# esp32-controller.net
KiCad netlist of a schematic drawn in EAGLE
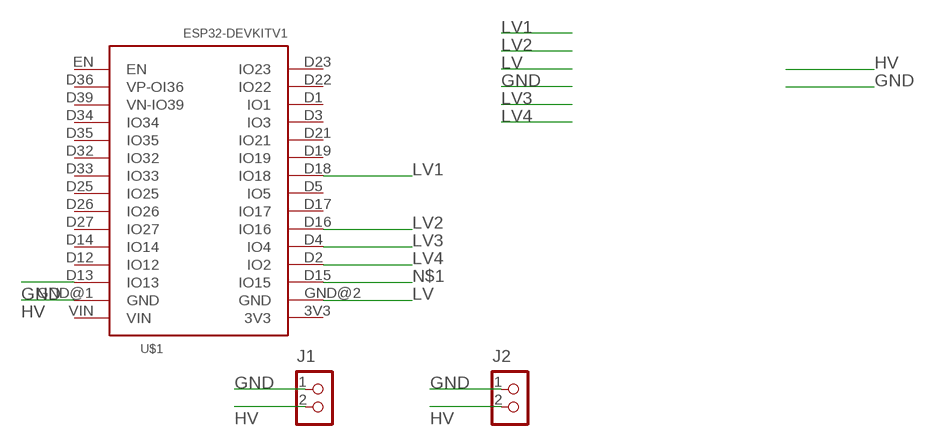
[diagram p0: schematic, sheet 1]

(export (version "E")
  (design (tool "Eeschema 10.0.6"))
  (components
    (comp (ref "J1")
      (value "CON_TERMINAL_BLOCK_02-5MM")
      (footprint "eagle-import:TERMINAL_BLOCK_2P_5")
      (libsource (lib "eagle-import") (part "CON_TERMINAL_BLOCK_02-5MM"))
    )
    (comp (ref "J2")
      (value "CON_TERMINAL_BLOCK_02-5MM")
      (footprint "eagle-import:TERMINAL_BLOCK_2P_5")
      (libsource (lib "eagle-import") (part "CON_TERMINAL_BLOCK_02-5MM"))
    )
    (comp (ref "U$1")
      (value "ESP32DEVKITV1")
      (footprint "eagle-import:ESP32-DEVKITV1")
      (libsource (lib "eagle-import") (part "ESP32DEVKITV1"))
    )
  )
  (nets
    (net (code "1") (name "/GND") (class "Default")
      (node (ref "J1") (pin "1") (pinfunction "1_1") (pintype "passive"))
      (node (ref "J2") (pin "1") (pinfunction "1_1") (pintype "passive"))
      (node (ref "U$1") (pin "D13") (pinfunction "IO13_D13") (pintype "bidirectional"))
    )
    (net (code "2") (name "/HV") (class "Default")
      (node (ref "J1") (pin "2") (pinfunction "2_2") (pintype "passive"))
      (node (ref "J2") (pin "2") (pinfunction "2_2") (pintype "passive"))
      (node (ref "U$1") (pin "GND@1") (pinfunction "GND_GND@1") (pintype "bidirectional"))
    )
    (net (code "3") (name "/LV") (class "Default")
      (node (ref "U$1") (pin "GND@2") (pinfunction "GND_GND@2") (pintype "bidirectional"))
    )
    (net (code "4") (name "/LV1") (class "Default")
      (node (ref "U$1") (pin "D18") (pinfunction "IO18_D18") (pintype "bidirectional"))
    )
    (net (code "5") (name "/LV2") (class "Default")
      (node (ref "U$1") (pin "D16") (pinfunction "IO16_D16") (pintype "bidirectional"))
    )
    (net (code "6") (name "/LV3") (class "Default")
      (node (ref "U$1") (pin "D4") (pinfunction "IO4_D4") (pintype "bidirectional"))
    )
    (net (code "7") (name "/LV4") (class "Default")
      (node (ref "U$1") (pin "D2") (pinfunction "IO2_D2") (pintype "bidirectional"))
    )
    (net (code "8") (name "/N$1") (class "Default")
      (node (ref "U$1") (pin "D15") (pinfunction "IO15_D15") (pintype "bidirectional"))
    )
    (net (code "9") (name "unconnected-(U$1-IO1-PadD1)") (class "Default")
      (node (ref "U$1") (pin "D1") (pinfunction "IO1_D1") (pintype "bidirectional"))
    )
    (net (code "10") (name "unconnected-(U$1-IO3-PadD3)") (class "Default")
      (node (ref "U$1") (pin "D3") (pinfunction "IO3_D3") (pintype "bidirectional"))
    )
    (net (code "11") (name "unconnected-(U$1-IO5-PadD5)") (class "Default")
      (node (ref "U$1") (pin "D5") (pinfunction "IO5_D5") (pintype "bidirectional"))
    )
    (net (code "12") (name "unconnected-(U$1-IO12-PadD12)") (class "Default")
      (node (ref "U$1") (pin "D12") (pinfunction "IO12_D12") (pintype "bidirectional"))
    )
    (net (code "13") (name "unconnected-(U$1-IO14-PadD14)") (class "Default")
      (node (ref "U$1") (pin "D14") (pinfunction "IO14_D14") (pintype "bidirectional"))
    )
    (net (code "14") (name "unconnected-(U$1-IO17-PadD17)") (class "Default")
      (node (ref "U$1") (pin "D17") (pinfunction "IO17_D17") (pintype "bidirectional"))
    )
    (net (code "15") (name "unconnected-(U$1-IO19-PadD19)") (class "Default")
      (node (ref "U$1") (pin "D19") (pinfunction "IO19_D19") (pintype "bidirectional"))
    )
    (net (code "16") (name "unconnected-(U$1-IO21-PadD21)") (class "Default")
      (node (ref "U$1") (pin "D21") (pinfunction "IO21_D21") (pintype "bidirectional"))
    )
    (net (code "17") (name "unconnected-(U$1-IO22-PadD22)") (class "Default")
      (node (ref "U$1") (pin "D22") (pinfunction "IO22_D22") (pintype "bidirectional"))
    )
    (net (code "18") (name "unconnected-(U$1-IO23-PadD23)") (class "Default")
      (node (ref "U$1") (pin "D23") (pinfunction "IO23_D23") (pintype "bidirectional"))
    )
    (net (code "19") (name "unconnected-(U$1-IO25-PadD25)") (class "Default")
      (node (ref "U$1") (pin "D25") (pinfunction "IO25_D25") (pintype "bidirectional"))
    )
    (net (code "20") (name "unconnected-(U$1-IO26-PadD26)") (class "Default")
      (node (ref "U$1") (pin "D26") (pinfunction "IO26_D26") (pintype "bidirectional"))
    )
    (net (code "21") (name "unconnected-(U$1-IO27-PadD27)") (class "Default")
      (node (ref "U$1") (pin "D27") (pinfunction "IO27_D27") (pintype "bidirectional"))
    )
    (net (code "22") (name "unconnected-(U$1-IO32-PadD32)") (class "Default")
      (node (ref "U$1") (pin "D32") (pinfunction "IO32_D32") (pintype "bidirectional"))
    )
    (net (code "23") (name "unconnected-(U$1-IO33-PadD33)") (class "Default")
      (node (ref "U$1") (pin "D33") (pinfunction "IO33_D33") (pintype "bidirectional"))
    )
    (net (code "24") (name "unconnected-(U$1-IO34-PadD34)") (class "Default")
      (node (ref "U$1") (pin "D34") (pinfunction "IO34_D34") (pintype "bidirectional"))
    )
    (net (code "25") (name "unconnected-(U$1-IO35-PadD35)") (class "Default")
      (node (ref "U$1") (pin "D35") (pinfunction "IO35_D35") (pintype "bidirectional"))
    )
    (net (code "26") (name "unconnected-(U$1-Pad3V3)") (class "Default")
      (node (ref "U$1") (pin "3V3") (pinfunction "3V3_3V3") (pintype "bidirectional"))
    )
    (net (code "27") (name "unconnected-(U$1-PadEN)") (class "Default")
      (node (ref "U$1") (pin "EN") (pinfunction "EN_EN") (pintype "bidirectional"))
    )
    (net (code "28") (name "unconnected-(U$1-PadVIN)") (class "Default")
      (node (ref "U$1") (pin "VIN") (pinfunction "VIN_VIN") (pintype "bidirectional"))
    )
    (net (code "29") (name "unconnected-(U$1-VN-IO39-PadD39)") (class "Default")
      (node (ref "U$1") (pin "D39") (pinfunction "VN-IO39_D39") (pintype "bidirectional"))
    )
    (net (code "30") (name "unconnected-(U$1-VP-OI36-PadD36)") (class "Default")
      (node (ref "U$1") (pin "D36") (pinfunction "VP-OI36_D36") (pintype "bidirectional"))
    )
  )
)
